# LPCB224_-_CORE_CONNECTOR.net
KiCad netlist of a schematic drawn in Altium Designer
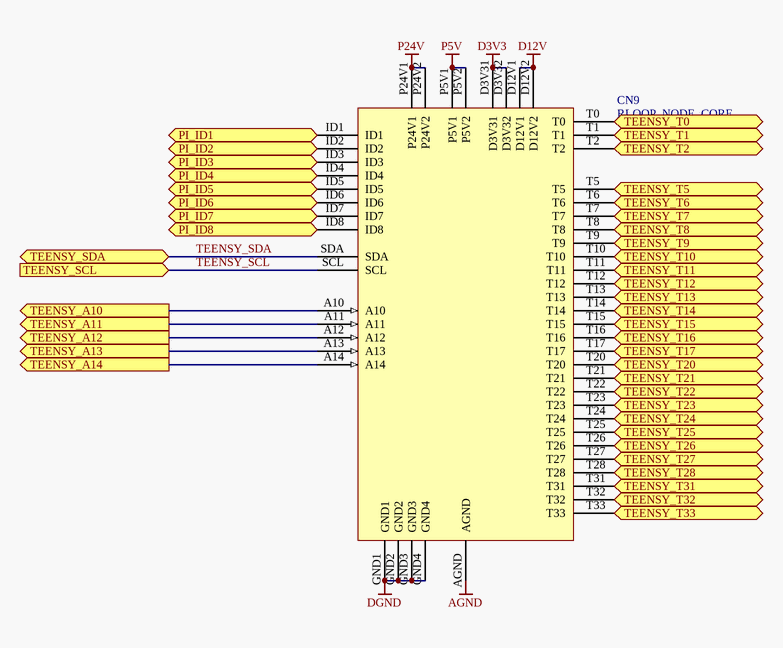
[diagram p0: LPCB224 - CORE CONNECTOR.SchDoc]

(export (version "E")
  (design (tool "Eeschema 10.0.6"))
  (components
    (comp (ref "CN9")
      (value "RLOOP_NODE_CORE")
      (footprint "RLOOP_NODE_CORE")
      (description "rLoop Node Core Connector")
      (libsource (lib "LDL_Connectors") (part "RLOOP_NODE_CORE"))
    )
  )
  (nets
    (net (code "1") (name "/PI_ID1") (class "Default")
      (node (ref "CN9") (pin "ID1") (pinfunction "ID1_ID1") (pintype "passive"))
    )
    (net (code "2") (name "/PI_ID2") (class "Default")
      (node (ref "CN9") (pin "ID2") (pinfunction "ID2_ID2") (pintype "passive"))
    )
    (net (code "3") (name "/PI_ID3") (class "Default")
      (node (ref "CN9") (pin "ID3") (pinfunction "ID3_ID3") (pintype "passive"))
    )
    (net (code "4") (name "/PI_ID4") (class "Default")
      (node (ref "CN9") (pin "ID4") (pinfunction "ID4_ID4") (pintype "passive"))
    )
    (net (code "5") (name "/PI_ID5") (class "Default")
      (node (ref "CN9") (pin "ID5") (pinfunction "ID5_ID5") (pintype "passive"))
    )
    (net (code "6") (name "/PI_ID6") (class "Default")
      (node (ref "CN9") (pin "ID6") (pinfunction "ID6_ID6") (pintype "passive"))
    )
    (net (code "7") (name "/PI_ID7") (class "Default")
      (node (ref "CN9") (pin "ID7") (pinfunction "ID7_ID7") (pintype "passive"))
    )
    (net (code "8") (name "/PI_ID8") (class "Default")
      (node (ref "CN9") (pin "ID8") (pinfunction "ID8_ID8") (pintype "passive"))
    )
    (net (code "9") (name "/TEENSY_A10") (class "Default")
      (node (ref "CN9") (pin "A10") (pinfunction "A10_A10") (pintype "input"))
    )
    (net (code "10") (name "/TEENSY_A11") (class "Default")
      (node (ref "CN9") (pin "A11") (pinfunction "A11_A11") (pintype "input"))
    )
    (net (code "11") (name "/TEENSY_A12") (class "Default")
      (node (ref "CN9") (pin "A12") (pinfunction "A12_A12") (pintype "input"))
    )
    (net (code "12") (name "/TEENSY_A13") (class "Default")
      (node (ref "CN9") (pin "A13") (pinfunction "A13_A13") (pintype "input"))
    )
    (net (code "13") (name "/TEENSY_A14") (class "Default")
      (node (ref "CN9") (pin "A14") (pinfunction "A14_A14") (pintype "input"))
    )
    (net (code "14") (name "/TEENSY_SCL") (class "Default")
      (node (ref "CN9") (pin "SCL") (pinfunction "SCL_SCL") (pintype "passive"))
    )
    (net (code "15") (name "/TEENSY_SDA") (class "Default")
      (node (ref "CN9") (pin "SDA") (pinfunction "SDA_SDA") (pintype "passive"))
    )
    (net (code "16") (name "/TEENSY_T0") (class "Default")
      (node (ref "CN9") (pin "T0") (pinfunction "T0_T0") (pintype "passive"))
    )
    (net (code "17") (name "/TEENSY_T1") (class "Default")
      (node (ref "CN9") (pin "T1") (pinfunction "T1_T1") (pintype "passive"))
    )
    (net (code "18") (name "/TEENSY_T2") (class "Default")
      (node (ref "CN9") (pin "T2") (pinfunction "T2_T2") (pintype "passive"))
    )
    (net (code "19") (name "/TEENSY_T5") (class "Default")
      (node (ref "CN9") (pin "T5") (pinfunction "T5_T5") (pintype "passive"))
    )
    (net (code "20") (name "/TEENSY_T6") (class "Default")
      (node (ref "CN9") (pin "T6") (pinfunction "T6_T6") (pintype "passive"))
    )
    (net (code "21") (name "/TEENSY_T7") (class "Default")
      (node (ref "CN9") (pin "T7") (pinfunction "T7_T7") (pintype "passive"))
    )
    (net (code "22") (name "/TEENSY_T8") (class "Default")
      (node (ref "CN9") (pin "T8") (pinfunction "T8_T8") (pintype "passive"))
    )
    (net (code "23") (name "/TEENSY_T9") (class "Default")
      (node (ref "CN9") (pin "T9") (pinfunction "T9_T9") (pintype "passive"))
    )
    (net (code "24") (name "/TEENSY_T10") (class "Default")
      (node (ref "CN9") (pin "T10") (pinfunction "T10_T10") (pintype "passive"))
    )
    (net (code "25") (name "/TEENSY_T11") (class "Default")
      (node (ref "CN9") (pin "T11") (pinfunction "T11_T11") (pintype "passive"))
    )
    (net (code "26") (name "/TEENSY_T12") (class "Default")
      (node (ref "CN9") (pin "T12") (pinfunction "T12_T12") (pintype "passive"))
    )
    (net (code "27") (name "/TEENSY_T13") (class "Default")
      (node (ref "CN9") (pin "T13") (pinfunction "T13_T13") (pintype "passive"))
    )
    (net (code "28") (name "/TEENSY_T14") (class "Default")
      (node (ref "CN9") (pin "T14") (pinfunction "T14_T14") (pintype "passive"))
    )
    (net (code "29") (name "/TEENSY_T15") (class "Default")
      (node (ref "CN9") (pin "T15") (pinfunction "T15_T15") (pintype "passive"))
    )
    (net (code "30") (name "/TEENSY_T16") (class "Default")
      (node (ref "CN9") (pin "T16") (pinfunction "T16_T16") (pintype "passive"))
    )
    (net (code "31") (name "/TEENSY_T17") (class "Default")
      (node (ref "CN9") (pin "T17") (pinfunction "T17_T17") (pintype "passive"))
    )
    (net (code "32") (name "/TEENSY_T20") (class "Default")
      (node (ref "CN9") (pin "T20") (pinfunction "T20_T20") (pintype "passive"))
    )
    (net (code "33") (name "/TEENSY_T21") (class "Default")
      (node (ref "CN9") (pin "T21") (pinfunction "T21_T21") (pintype "passive"))
    )
    (net (code "34") (name "/TEENSY_T22") (class "Default")
      (node (ref "CN9") (pin "T22") (pinfunction "T22_T22") (pintype "passive"))
    )
    (net (code "35") (name "/TEENSY_T23") (class "Default")
      (node (ref "CN9") (pin "T23") (pinfunction "T23_T23") (pintype "passive"))
    )
    (net (code "36") (name "/TEENSY_T24") (class "Default")
      (node (ref "CN9") (pin "T24") (pinfunction "T24_T24") (pintype "passive"))
    )
    (net (code "37") (name "/TEENSY_T25") (class "Default")
      (node (ref "CN9") (pin "T25") (pinfunction "T25_T25") (pintype "passive"))
    )
    (net (code "38") (name "/TEENSY_T26") (class "Default")
      (node (ref "CN9") (pin "T26") (pinfunction "T26_T26") (pintype "passive"))
    )
    (net (code "39") (name "/TEENSY_T27") (class "Default")
      (node (ref "CN9") (pin "T27") (pinfunction "T27_T27") (pintype "passive"))
    )
    (net (code "40") (name "/TEENSY_T28") (class "Default")
      (node (ref "CN9") (pin "T28") (pinfunction "T28_T28") (pintype "passive"))
    )
    (net (code "41") (name "/TEENSY_T31") (class "Default")
      (node (ref "CN9") (pin "T31") (pinfunction "T31_T31") (pintype "passive"))
    )
    (net (code "42") (name "/TEENSY_T32") (class "Default")
      (node (ref "CN9") (pin "T32") (pinfunction "T32_T32") (pintype "passive"))
    )
    (net (code "43") (name "/TEENSY_T33") (class "Default")
      (node (ref "CN9") (pin "T33") (pinfunction "T33_T33") (pintype "passive"))
    )
    (net (code "44") (name "AGND") (class "Default")
      (node (ref "CN9") (pin "AGND") (pinfunction "AGND_AGND") (pintype "power_in"))
    )
    (net (code "45") (name "D3V3") (class "Default")
      (node (ref "CN9") (pin "D3V31") (pinfunction "D3V31_D3V31") (pintype "power_in"))
      (node (ref "CN9") (pin "D3V32") (pinfunction "D3V32_D3V32") (pintype "power_in"))
    )
    (net (code "46") (name "D12V") (class "Default")
      (node (ref "CN9") (pin "D12V1") (pinfunction "D12V1_D12V1") (pintype "power_in"))
      (node (ref "CN9") (pin "D12V2") (pinfunction "D12V2_D12V2") (pintype "power_in"))
    )
    (net (code "47") (name "DGND") (class "Default")
      (node (ref "CN9") (pin "GND1") (pinfunction "GND1_GND1") (pintype "power_in"))
      (node (ref "CN9") (pin "GND2") (pinfunction "GND2_GND2") (pintype "power_in"))
      (node (ref "CN9") (pin "GND3") (pinfunction "GND3_GND3") (pintype "power_in"))
      (node (ref "CN9") (pin "GND4") (pinfunction "GND4_GND4") (pintype "power_in"))
    )
    (net (code "48") (name "P5V") (class "Default")
      (node (ref "CN9") (pin "P5V1") (pinfunction "P5V1_P5V1") (pintype "power_in"))
      (node (ref "CN9") (pin "P5V2") (pinfunction "P5V2_P5V2") (pintype "power_in"))
    )
    (net (code "49") (name "P24V") (class "Default")
      (node (ref "CN9") (pin "P24V1") (pinfunction "P24V1_P24V1") (pintype "power_in"))
      (node (ref "CN9") (pin "P24V2") (pinfunction "P24V2_P24V2") (pintype "power_in"))
    )
  )
)
